# heliostat.net
KiCad netlist of a schematic drawn in EAGLE
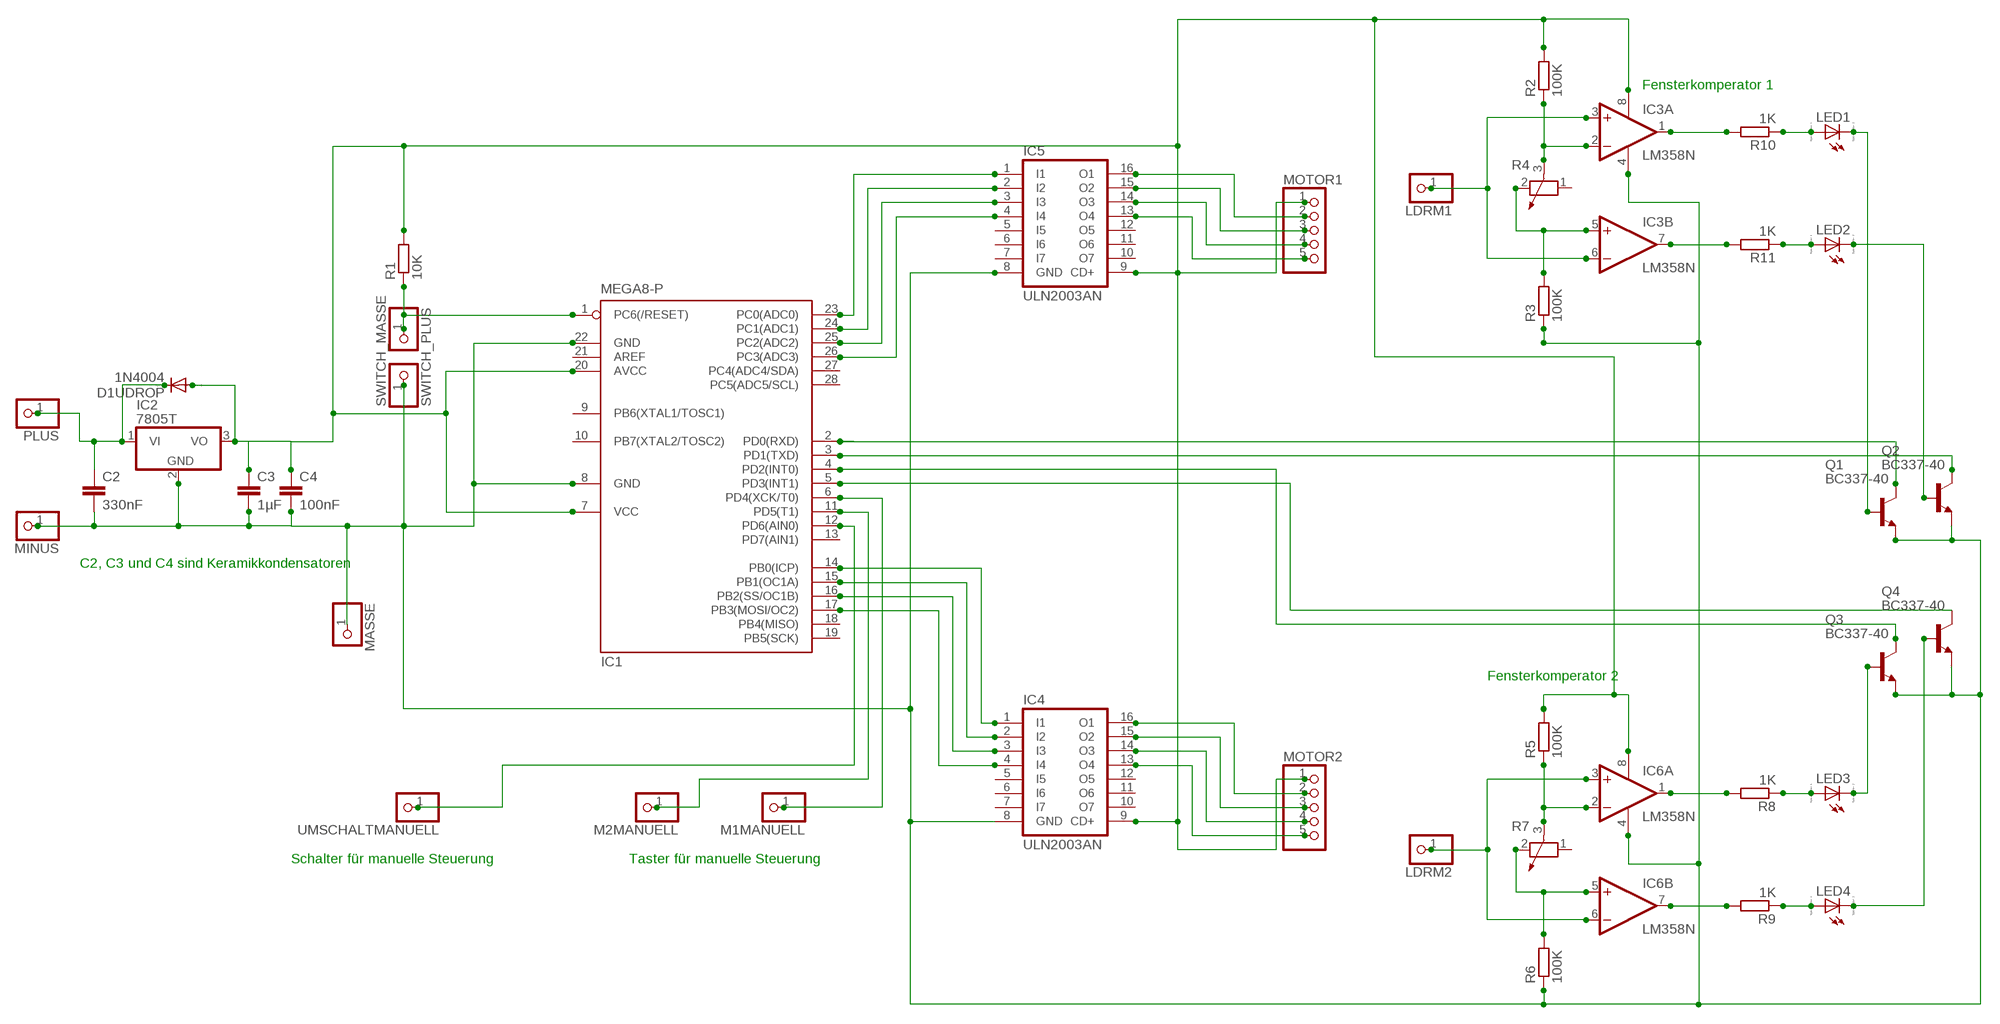
[diagram p0: schematic, sheet 1]

(export (version "E")
  (design (tool "Eeschema 10.0.6"))
  (components
    (comp (ref "C2")
      (value "330nF")
      (footprint "eagle-import:C025-024X044")
      (libsource (lib "eagle-import") (part "C-EU025-024X044"))
    )
    (comp (ref "C3")
      (value "1µF")
      (footprint "eagle-import:C025-024X044")
      (libsource (lib "eagle-import") (part "C-EU025-024X044"))
    )
    (comp (ref "C4")
      (value "100nF")
      (footprint "eagle-import:C025-024X044")
      (libsource (lib "eagle-import") (part "C-EU025-024X044"))
    )
    (comp (ref "D1UDROP")
      (value "1N4004")
      (footprint "eagle-import:DO41-10")
      (libsource (lib "eagle-import") (part "1N4004"))
    )
    (comp (ref "IC1")
      (value "MEGA8-P")
      (footprint "eagle-import:DIL28-3")
      (libsource (lib "eagle-import") (part "MEGA8-P"))
    )
    (comp (ref "IC2")
      (value "7805T")
      (footprint "eagle-import:TO220H")
      (libsource (lib "eagle-import") (part "78T05"))
    )
    (comp (ref "IC3")
      (value "LM358N")
      (footprint "eagle-import:DIL08")
      (libsource (lib "eagle-import") (part "LM358N"))
    )
    (comp (ref "IC4")
      (value "ULN2003AN")
      (footprint "eagle-import:DIL16")
      (libsource (lib "eagle-import") (part "ULN2003AN"))
    )
    (comp (ref "IC5")
      (value "ULN2003AN")
      (footprint "eagle-import:DIL16")
      (libsource (lib "eagle-import") (part "ULN2003AN"))
    )
    (comp (ref "IC6")
      (value "LM358N")
      (footprint "eagle-import:DIL08")
      (libsource (lib "eagle-import") (part "LM358N"))
    )
    (comp (ref "LDRM1")
      (value "PINHD-1X1")
      (footprint "eagle-import:1X01")
      (libsource (lib "eagle-import") (part "PINHD-1X1"))
    )
    (comp (ref "LDRM2")
      (value "PINHD-1X1")
      (footprint "eagle-import:1X01")
      (libsource (lib "eagle-import") (part "PINHD-1X1"))
    )
    (comp (ref "LED1")
      (value "LED_ELD260")
      (footprint "eagle-import:LED_LD260")
      (libsource (lib "eagle-import") (part "LED_ELD260"))
    )
    (comp (ref "LED2")
      (value "LED_ELD260")
      (footprint "eagle-import:LED_LD260")
      (libsource (lib "eagle-import") (part "LED_ELD260"))
    )
    (comp (ref "LED3")
      (value "LED_ELD260")
      (footprint "eagle-import:LED_LD260")
      (libsource (lib "eagle-import") (part "LED_ELD260"))
    )
    (comp (ref "LED4")
      (value "LED_ELD260")
      (footprint "eagle-import:LED_LD260")
      (libsource (lib "eagle-import") (part "LED_ELD260"))
    )
    (comp (ref "M1MANUELL")
      (value "PINHD-1X1")
      (footprint "eagle-import:1X01")
      (libsource (lib "eagle-import") (part "PINHD-1X1"))
    )
    (comp (ref "M2MANUELL")
      (value "PINHD-1X1")
      (footprint "eagle-import:1X01")
      (libsource (lib "eagle-import") (part "PINHD-1X1"))
    )
    (comp (ref "MASSE")
      (value "PINHD-1X1")
      (footprint "eagle-import:1X01")
      (libsource (lib "eagle-import") (part "PINHD-1X1"))
    )
    (comp (ref "MINUS")
      (value "PINHD-1X1")
      (footprint "eagle-import:1X01")
      (libsource (lib "eagle-import") (part "PINHD-1X1"))
    )
    (comp (ref "MOTOR1")
      (value "PINHD-1X5")
      (footprint "eagle-import:1X05")
      (libsource (lib "eagle-import") (part "PINHD-1X5"))
    )
    (comp (ref "MOTOR2")
      (value "PINHD-1X5")
      (footprint "eagle-import:1X05")
      (libsource (lib "eagle-import") (part "PINHD-1X5"))
    )
    (comp (ref "PLUS")
      (value "PINHD-1X1")
      (footprint "eagle-import:1X01")
      (libsource (lib "eagle-import") (part "PINHD-1X1"))
    )
    (comp (ref "Q1")
      (value "BC337-40")
      (footprint "eagle-import:TO92")
      (libsource (lib "eagle-import") (part "BC337-40"))
    )
    (comp (ref "Q2")
      (value "BC337-40")
      (footprint "eagle-import:TO92")
      (libsource (lib "eagle-import") (part "BC337-40"))
    )
    (comp (ref "Q3")
      (value "BC337-40")
      (footprint "eagle-import:TO92")
      (libsource (lib "eagle-import") (part "BC337-40"))
    )
    (comp (ref "Q4")
      (value "BC337-40")
      (footprint "eagle-import:TO92")
      (libsource (lib "eagle-import") (part "BC337-40"))
    )
    (comp (ref "R1")
      (value "10K")
      (footprint "eagle-import:0204V")
      (libsource (lib "eagle-import") (part "R-EU_0204/2V"))
    )
    (comp (ref "R2")
      (value "100K")
      (footprint "eagle-import:0204V")
      (libsource (lib "eagle-import") (part "R-EU_0204/2V"))
    )
    (comp (ref "R3")
      (value "100K")
      (footprint "eagle-import:0204V")
      (libsource (lib "eagle-import") (part "R-EU_0204/2V"))
    )
    (comp (ref "R4")
      (value "POTENTIOMETER_PT-10")
      (footprint "eagle-import:PT-10")
      (libsource (lib "eagle-import") (part "POTENTIOMETER_PT-10"))
    )
    (comp (ref "R5")
      (value "100K")
      (footprint "eagle-import:0204V")
      (libsource (lib "eagle-import") (part "R-EU_0204/2V"))
    )
    (comp (ref "R6")
      (value "100K")
      (footprint "eagle-import:0204V")
      (libsource (lib "eagle-import") (part "R-EU_0204/2V"))
    )
    (comp (ref "R7")
      (value "POTENTIOMETER_PT-10")
      (footprint "eagle-import:PT-10")
      (libsource (lib "eagle-import") (part "POTENTIOMETER_PT-10"))
    )
    (comp (ref "R8")
      (value "1K")
      (footprint "eagle-import:0204V")
      (libsource (lib "eagle-import") (part "R-EU_0204/2V"))
    )
    (comp (ref "R9")
      (value "1K")
      (footprint "eagle-import:0204V")
      (libsource (lib "eagle-import") (part "R-EU_0204/2V"))
    )
    (comp (ref "R10")
      (value "1K")
      (footprint "eagle-import:0204V")
      (libsource (lib "eagle-import") (part "R-EU_0204/2V"))
    )
    (comp (ref "R11")
      (value "1K")
      (footprint "eagle-import:0204V")
      (libsource (lib "eagle-import") (part "R-EU_0204/2V"))
    )
    (comp (ref "SWITCH_MASSE")
      (value "PINHD-1X1")
      (footprint "eagle-import:1X01")
      (libsource (lib "eagle-import") (part "PINHD-1X1"))
    )
    (comp (ref "SWITCH_PLUS")
      (value "PINHD-1X1")
      (footprint "eagle-import:1X01")
      (libsource (lib "eagle-import") (part "PINHD-1X1"))
    )
    (comp (ref "UMSCHALTMANUELL")
      (value "PINHD-1X1")
      (footprint "eagle-import:1X01")
      (libsource (lib "eagle-import") (part "PINHD-1X1"))
    )
  )
  (nets
    (net (code "1") (name "Net-(IC1-AVCC)") (class "Default")
      (node (ref "C3") (pin "1") (pinfunction "1_1") (pintype "passive"))
      (node (ref "C4") (pin "1") (pinfunction "1_1") (pintype "passive"))
      (node (ref "D1UDROP") (pin "A") (pinfunction "A_A") (pintype "passive"))
      (node (ref "IC1") (pin "20") (pinfunction "AVCC_20") (pintype "power_in"))
      (node (ref "IC1") (pin "7") (pinfunction "VCC_7") (pintype "power_in"))
      (node (ref "IC2") (pin "3") (pinfunction "VO_3") (pintype "passive"))
      (node (ref "IC3") (pin "8") (pinfunction "V+_8") (pintype "power_in"))
      (node (ref "IC4") (pin "9") (pinfunction "CD+_9") (pintype "passive"))
      (node (ref "IC5") (pin "9") (pinfunction "CD+_9") (pintype "passive"))
      (node (ref "IC6") (pin "8") (pinfunction "V+_8") (pintype "power_in"))
      (node (ref "MOTOR1") (pin "1") (pinfunction "1_1") (pintype "passive"))
      (node (ref "MOTOR2") (pin "1") (pinfunction "1_1") (pintype "passive"))
      (node (ref "R1") (pin "2") (pinfunction "2_2") (pintype "passive"))
      (node (ref "R2") (pin "2") (pinfunction "2_2") (pintype "passive"))
      (node (ref "R5") (pin "2") (pinfunction "2_2") (pintype "passive"))
    )
    (net (code "2") (name "Net-(IC1-PB0(ICP))") (class "Default")
      (node (ref "IC1") (pin "14") (pinfunction "PB0(ICP)_14") (pintype "bidirectional"))
      (node (ref "IC4") (pin "1") (pinfunction "I1_1") (pintype "input"))
    )
    (net (code "3") (name "Net-(IC1-PB1(OC1A))") (class "Default")
      (node (ref "IC1") (pin "15") (pinfunction "PB1(OC1A)_15") (pintype "bidirectional"))
      (node (ref "IC4") (pin "2") (pinfunction "I2_2") (pintype "input"))
    )
    (net (code "4") (name "Net-(IC1-PB2(SS{slash}OC1B))") (class "Default")
      (node (ref "IC1") (pin "16") (pinfunction "PB2(SS/OC1B)_16") (pintype "bidirectional"))
      (node (ref "IC4") (pin "3") (pinfunction "I3_3") (pintype "input"))
    )
    (net (code "5") (name "Net-(IC1-PB3(MOSI{slash}OC2))") (class "Default")
      (node (ref "IC1") (pin "17") (pinfunction "PB3(MOSI/OC2)_17") (pintype "bidirectional"))
      (node (ref "IC4") (pin "4") (pinfunction "I4_4") (pintype "input"))
    )
    (net (code "6") (name "Net-(IC1-PC0(ADC0))") (class "Default")
      (node (ref "IC1") (pin "23") (pinfunction "PC0(ADC0)_23") (pintype "bidirectional"))
      (node (ref "IC5") (pin "1") (pinfunction "I1_1") (pintype "input"))
    )
    (net (code "7") (name "Net-(IC1-PC1(ADC1))") (class "Default")
      (node (ref "IC1") (pin "24") (pinfunction "PC1(ADC1)_24") (pintype "bidirectional"))
      (node (ref "IC5") (pin "2") (pinfunction "I2_2") (pintype "input"))
    )
    (net (code "8") (name "Net-(IC1-PC2(ADC2))") (class "Default")
      (node (ref "IC1") (pin "25") (pinfunction "PC2(ADC2)_25") (pintype "bidirectional"))
      (node (ref "IC5") (pin "3") (pinfunction "I3_3") (pintype "input"))
    )
    (net (code "9") (name "Net-(IC1-PC3(ADC3))") (class "Default")
      (node (ref "IC1") (pin "26") (pinfunction "PC3(ADC3)_26") (pintype "bidirectional"))
      (node (ref "IC5") (pin "4") (pinfunction "I4_4") (pintype "input"))
    )
    (net (code "10") (name "Net-(IC1-PC6({slash}RESET))") (class "Default")
      (node (ref "IC1") (pin "1") (pinfunction "PC6(/RESET)_1") (pintype "bidirectional"))
      (node (ref "R1") (pin "1") (pinfunction "1_1") (pintype "passive"))
      (node (ref "SWITCH_PLUS") (pin "1") (pinfunction "1_1") (pintype "passive"))
    )
    (net (code "11") (name "Net-(IC1-PD0(RXD))") (class "Default")
      (node (ref "IC1") (pin "2") (pinfunction "PD0(RXD)_2") (pintype "bidirectional"))
      (node (ref "Q1") (pin "3") (pinfunction "C_3") (pintype "passive"))
    )
    (net (code "12") (name "Net-(IC1-PD1(TXD))") (class "Default")
      (node (ref "IC1") (pin "3") (pinfunction "PD1(TXD)_3") (pintype "bidirectional"))
      (node (ref "Q2") (pin "3") (pinfunction "C_3") (pintype "passive"))
    )
    (net (code "13") (name "Net-(IC1-PD2(INT0))") (class "Default")
      (node (ref "IC1") (pin "4") (pinfunction "PD2(INT0)_4") (pintype "bidirectional"))
      (node (ref "Q3") (pin "3") (pinfunction "C_3") (pintype "passive"))
    )
    (net (code "14") (name "Net-(IC1-PD3(INT1))") (class "Default")
      (node (ref "IC1") (pin "5") (pinfunction "PD3(INT1)_5") (pintype "bidirectional"))
      (node (ref "Q4") (pin "3") (pinfunction "C_3") (pintype "passive"))
    )
    (net (code "15") (name "Net-(IC1-PD4(XCK{slash}T0))") (class "Default")
      (node (ref "IC1") (pin "6") (pinfunction "PD4(XCK/T0)_6") (pintype "bidirectional"))
      (node (ref "M1MANUELL") (pin "1") (pinfunction "1_1") (pintype "passive"))
    )
    (net (code "16") (name "Net-(IC1-PD5(T1))") (class "Default")
      (node (ref "IC1") (pin "11") (pinfunction "PD5(T1)_11") (pintype "bidirectional"))
      (node (ref "M2MANUELL") (pin "1") (pinfunction "1_1") (pintype "passive"))
    )
    (net (code "17") (name "Net-(IC1-PD6(AIN0))") (class "Default")
      (node (ref "IC1") (pin "12") (pinfunction "PD6(AIN0)_12") (pintype "bidirectional"))
      (node (ref "UMSCHALTMANUELL") (pin "1") (pinfunction "1_1") (pintype "passive"))
    )
    (net (code "18") (name "Net-(IC2-GND)") (class "Default")
      (node (ref "C2") (pin "2") (pinfunction "2_2") (pintype "passive"))
      (node (ref "C3") (pin "2") (pinfunction "2_2") (pintype "passive"))
      (node (ref "C4") (pin "2") (pinfunction "2_2") (pintype "passive"))
      (node (ref "IC1") (pin "22") (pinfunction "GND_22") (pintype "power_in"))
      (node (ref "IC1") (pin "8") (pinfunction "GND_8") (pintype "power_in"))
      (node (ref "IC2") (pin "2") (pinfunction "GND_2") (pintype "passive"))
      (node (ref "IC3") (pin "4") (pinfunction "V-_4") (pintype "power_in"))
      (node (ref "IC4") (pin "8") (pinfunction "GND_8") (pintype "power_in"))
      (node (ref "IC5") (pin "8") (pinfunction "GND_8") (pintype "power_in"))
      (node (ref "IC6") (pin "4") (pinfunction "V-_4") (pintype "power_in"))
      (node (ref "MASSE") (pin "1") (pinfunction "1_1") (pintype "passive"))
      (node (ref "MINUS") (pin "1") (pinfunction "1_1") (pintype "passive"))
      (node (ref "Q1") (pin "1") (pinfunction "E_1") (pintype "passive"))
      (node (ref "Q2") (pin "1") (pinfunction "E_1") (pintype "passive"))
      (node (ref "Q3") (pin "1") (pinfunction "E_1") (pintype "passive"))
      (node (ref "Q4") (pin "1") (pinfunction "E_1") (pintype "passive"))
      (node (ref "R3") (pin "1") (pinfunction "1_1") (pintype "passive"))
      (node (ref "R6") (pin "1") (pinfunction "1_1") (pintype "passive"))
      (node (ref "SWITCH_MASSE") (pin "1") (pinfunction "1_1") (pintype "passive"))
    )
    (net (code "19") (name "Net-(IC2-VI)") (class "Default")
      (node (ref "C2") (pin "1") (pinfunction "1_1") (pintype "passive"))
      (node (ref "D1UDROP") (pin "C") (pinfunction "C_C") (pintype "passive"))
      (node (ref "IC2") (pin "1") (pinfunction "VI_1") (pintype "input"))
      (node (ref "PLUS") (pin "1") (pinfunction "1_1") (pintype "passive"))
    )
    (net (code "20") (name "Net-(IC3A-+IN)") (class "Default")
      (node (ref "IC3") (pin "3") (pinfunction "+IN_3") (pintype "input"))
      (node (ref "IC3") (pin "6") (pinfunction "-IN_6") (pintype "input"))
      (node (ref "LDRM1") (pin "1") (pinfunction "1_1") (pintype "passive"))
    )
    (net (code "21") (name "Net-(IC3A--IN)") (class "Default")
      (node (ref "IC3") (pin "2") (pinfunction "-IN_2") (pintype "input"))
      (node (ref "R2") (pin "1") (pinfunction "1_1") (pintype "passive"))
      (node (ref "R4") (pin "3") (pinfunction "3_3") (pintype "passive"))
    )
    (net (code "22") (name "Net-(IC3A-OUT)") (class "Default")
      (node (ref "IC3") (pin "1") (pinfunction "OUT_1") (pintype "output"))
      (node (ref "R10") (pin "2") (pinfunction "2_2") (pintype "passive"))
    )
    (net (code "23") (name "Net-(IC3B-+IN)") (class "Default")
      (node (ref "IC3") (pin "5") (pinfunction "+IN_5") (pintype "input"))
      (node (ref "R3") (pin "2") (pinfunction "2_2") (pintype "passive"))
      (node (ref "R4") (pin "2") (pinfunction "2_2") (pintype "passive"))
    )
    (net (code "24") (name "Net-(IC3B-OUT)") (class "Default")
      (node (ref "IC3") (pin "7") (pinfunction "OUT_7") (pintype "output"))
      (node (ref "R11") (pin "2") (pinfunction "2_2") (pintype "passive"))
    )
    (net (code "25") (name "Net-(IC4-O1)") (class "Default")
      (node (ref "IC4") (pin "16") (pinfunction "O1_16") (pintype "open_collector"))
      (node (ref "MOTOR2") (pin "2") (pinfunction "2_2") (pintype "passive"))
    )
    (net (code "26") (name "Net-(IC4-O2)") (class "Default")
      (node (ref "IC4") (pin "15") (pinfunction "O2_15") (pintype "open_collector"))
      (node (ref "MOTOR2") (pin "3") (pinfunction "3_3") (pintype "passive"))
    )
    (net (code "27") (name "Net-(IC4-O3)") (class "Default")
      (node (ref "IC4") (pin "14") (pinfunction "O3_14") (pintype "open_collector"))
      (node (ref "MOTOR2") (pin "4") (pinfunction "4_4") (pintype "passive"))
    )
    (net (code "28") (name "Net-(IC4-O4)") (class "Default")
      (node (ref "IC4") (pin "13") (pinfunction "O4_13") (pintype "open_collector"))
      (node (ref "MOTOR2") (pin "5") (pinfunction "5_5") (pintype "passive"))
    )
    (net (code "29") (name "Net-(IC5-O1)") (class "Default")
      (node (ref "IC5") (pin "16") (pinfunction "O1_16") (pintype "open_collector"))
      (node (ref "MOTOR1") (pin "2") (pinfunction "2_2") (pintype "passive"))
    )
    (net (code "30") (name "Net-(IC5-O2)") (class "Default")
      (node (ref "IC5") (pin "15") (pinfunction "O2_15") (pintype "open_collector"))
      (node (ref "MOTOR1") (pin "3") (pinfunction "3_3") (pintype "passive"))
    )
    (net (code "31") (name "Net-(IC5-O3)") (class "Default")
      (node (ref "IC5") (pin "14") (pinfunction "O3_14") (pintype "open_collector"))
      (node (ref "MOTOR1") (pin "4") (pinfunction "4_4") (pintype "passive"))
    )
    (net (code "32") (name "Net-(IC5-O4)") (class "Default")
      (node (ref "IC5") (pin "13") (pinfunction "O4_13") (pintype "open_collector"))
      (node (ref "MOTOR1") (pin "5") (pinfunction "5_5") (pintype "passive"))
    )
    (net (code "33") (name "Net-(IC6A-+IN)") (class "Default")
      (node (ref "IC6") (pin "3") (pinfunction "+IN_3") (pintype "input"))
      (node (ref "IC6") (pin "6") (pinfunction "-IN_6") (pintype "input"))
      (node (ref "LDRM2") (pin "1") (pinfunction "1_1") (pintype "passive"))
    )
    (net (code "34") (name "Net-(IC6A--IN)") (class "Default")
      (node (ref "IC6") (pin "2") (pinfunction "-IN_2") (pintype "input"))
      (node (ref "R5") (pin "1") (pinfunction "1_1") (pintype "passive"))
      (node (ref "R7") (pin "3") (pinfunction "3_3") (pintype "passive"))
    )
    (net (code "35") (name "Net-(IC6A-OUT)") (class "Default")
      (node (ref "IC6") (pin "1") (pinfunction "OUT_1") (pintype "output"))
      (node (ref "R8") (pin "2") (pinfunction "2_2") (pintype "passive"))
    )
    (net (code "36") (name "Net-(IC6B-+IN)") (class "Default")
      (node (ref "IC6") (pin "5") (pinfunction "+IN_5") (pintype "input"))
      (node (ref "R6") (pin "2") (pinfunction "2_2") (pintype "passive"))
      (node (ref "R7") (pin "2") (pinfunction "2_2") (pintype "passive"))
    )
    (net (code "37") (name "Net-(IC6B-OUT)") (class "Default")
      (node (ref "IC6") (pin "7") (pinfunction "OUT_7") (pintype "output"))
      (node (ref "R9") (pin "2") (pinfunction "2_2") (pintype "passive"))
    )
    (net (code "38") (name "Net-(LED1-C)") (class "Default")
      (node (ref "LED1") (pin "K") (pinfunction "C_K") (pintype "passive"))
      (node (ref "Q1") (pin "2") (pinfunction "B_2") (pintype "passive"))
    )
    (net (code "39") (name "Net-(LED1-PadA)") (class "Default")
      (node (ref "LED1") (pin "A") (pinfunction "A_A") (pintype "passive"))
      (node (ref "R10") (pin "1") (pinfunction "1_1") (pintype "passive"))
    )
    (net (code "40") (name "Net-(LED2-C)") (class "Default")
      (node (ref "LED2") (pin "K") (pinfunction "C_K") (pintype "passive"))
      (node (ref "Q2") (pin "2") (pinfunction "B_2") (pintype "passive"))
    )
    (net (code "41") (name "Net-(LED2-PadA)") (class "Default")
      (node (ref "LED2") (pin "A") (pinfunction "A_A") (pintype "passive"))
      (node (ref "R11") (pin "1") (pinfunction "1_1") (pintype "passive"))
    )
    (net (code "42") (name "Net-(LED3-C)") (class "Default")
      (node (ref "LED3") (pin "K") (pinfunction "C_K") (pintype "passive"))
      (node (ref "Q3") (pin "2") (pinfunction "B_2") (pintype "passive"))
    )
    (net (code "43") (name "Net-(LED3-PadA)") (class "Default")
      (node (ref "LED3") (pin "A") (pinfunction "A_A") (pintype "passive"))
      (node (ref "R8") (pin "1") (pinfunction "1_1") (pintype "passive"))
    )
    (net (code "44") (name "Net-(LED4-C)") (class "Default")
      (node (ref "LED4") (pin "K") (pinfunction "C_K") (pintype "passive"))
      (node (ref "Q4") (pin "2") (pinfunction "B_2") (pintype "passive"))
    )
    (net (code "45") (name "Net-(LED4-PadA)") (class "Default")
      (node (ref "LED4") (pin "A") (pinfunction "A_A") (pintype "passive"))
      (node (ref "R9") (pin "1") (pinfunction "1_1") (pintype "passive"))
    )
    (net (code "46") (name "unconnected-(IC1-AREF-Pad21)") (class "Default")
      (node (ref "IC1") (pin "21") (pinfunction "AREF_21") (pintype "passive"))
    )
    (net (code "47") (name "unconnected-(IC1-PB4(MISO)-Pad18)") (class "Default")
      (node (ref "IC1") (pin "18") (pinfunction "PB4(MISO)_18") (pintype "bidirectional"))
    )
    (net (code "48") (name "unconnected-(IC1-PB5(SCK)-Pad19)") (class "Default")
      (node (ref "IC1") (pin "19") (pinfunction "PB5(SCK)_19") (pintype "bidirectional"))
    )
    (net (code "49") (name "unconnected-(IC1-PB6(XTAL1{slash}TOSC1)-Pad9)") (class "Default")
      (node (ref "IC1") (pin "9") (pinfunction "PB6(XTAL1/TOSC1)_9") (pintype "bidirectional"))
    )
    (net (code "50") (name "unconnected-(IC1-PB7(XTAL2{slash}TOSC2)-Pad10)") (class "Default")
      (node (ref "IC1") (pin "10") (pinfunction "PB7(XTAL2/TOSC2)_10") (pintype "bidirectional"))
    )
    (net (code "51") (name "unconnected-(IC1-PC4(ADC4{slash}SDA)-Pad27)") (class "Default")
      (node (ref "IC1") (pin "27") (pinfunction "PC4(ADC4/SDA)_27") (pintype "bidirectional"))
    )
    (net (code "52") (name "unconnected-(IC1-PC5(ADC5{slash}SCL)-Pad28)") (class "Default")
      (node (ref "IC1") (pin "28") (pinfunction "PC5(ADC5/SCL)_28") (pintype "bidirectional"))
    )
    (net (code "53") (name "unconnected-(IC1-PD7(AIN1)-Pad13)") (class "Default")
      (node (ref "IC1") (pin "13") (pinfunction "PD7(AIN1)_13") (pintype "bidirectional"))
    )
    (net (code "54") (name "unconnected-(IC4-I5-Pad5)") (class "Default")
      (node (ref "IC4") (pin "5") (pinfunction "I5_5") (pintype "input"))
    )
    (net (code "55") (name "unconnected-(IC4-I6-Pad6)") (class "Default")
      (node (ref "IC4") (pin "6") (pinfunction "I6_6") (pintype "input"))
    )
    (net (code "56") (name "unconnected-(IC4-I7-Pad7)") (class "Default")
      (node (ref "IC4") (pin "7") (pinfunction "I7_7") (pintype "input"))
    )
    (net (code "57") (name "unconnected-(IC4-O5-Pad12)") (class "Default")
      (node (ref "IC4") (pin "12") (pinfunction "O5_12") (pintype "open_collector"))
    )
    (net (code "58") (name "unconnected-(IC4-O6-Pad11)") (class "Default")
      (node (ref "IC4") (pin "11") (pinfunction "O6_11") (pintype "open_collector"))
    )
    (net (code "59") (name "unconnected-(IC4-O7-Pad10)") (class "Default")
      (node (ref "IC4") (pin "10") (pinfunction "O7_10") (pintype "open_collector"))
    )
    (net (code "60") (name "unconnected-(IC5-I5-Pad5)") (class "Default")
      (node (ref "IC5") (pin "5") (pinfunction "I5_5") (pintype "input"))
    )
    (net (code "61") (name "unconnected-(IC5-I6-Pad6)") (class "Default")
      (node (ref "IC5") (pin "6") (pinfunction "I6_6") (pintype "input"))
    )
    (net (code "62") (name "unconnected-(IC5-I7-Pad7)") (class "Default")
      (node (ref "IC5") (pin "7") (pinfunction "I7_7") (pintype "input"))
    )
    (net (code "63") (name "unconnected-(IC5-O5-Pad12)") (class "Default")
      (node (ref "IC5") (pin "12") (pinfunction "O5_12") (pintype "open_collector"))
    )
    (net (code "64") (name "unconnected-(IC5-O6-Pad11)") (class "Default")
      (node (ref "IC5") (pin "11") (pinfunction "O6_11") (pintype "open_collector"))
    )
    (net (code "65") (name "unconnected-(IC5-O7-Pad10)") (class "Default")
      (node (ref "IC5") (pin "10") (pinfunction "O7_10") (pintype "open_collector"))
    )
    (net (code "66") (name "unconnected-(R4-Pad1)") (class "Default")
      (node (ref "R4") (pin "1") (pinfunction "1_1") (pintype "passive"))
    )
    (net (code "67") (name "unconnected-(R7-Pad1)") (class "Default")
      (node (ref "R7") (pin "1") (pinfunction "1_1") (pintype "passive"))
    )
  )
)
